# neopixels.net
KiCad netlist of a schematic drawn in Altium Designer
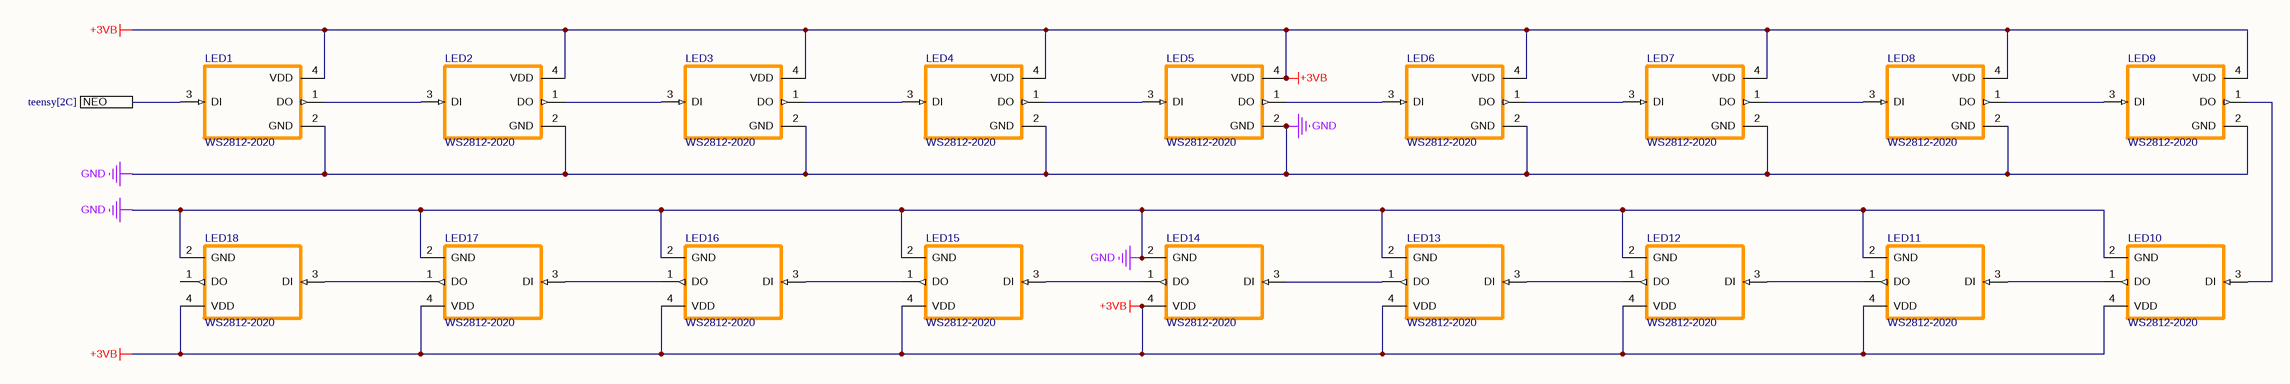
[diagram p0: neopixels.SchDoc]

(export (version "E")
  (design (tool "Eeschema 10.0.6"))
  (components
    (comp (ref "LED1")
      (value "WS2812-2020")
      (footprint "WS2812-2020")
      (libsource (lib "") (part "WS2812-2020_1"))
    )
    (comp (ref "LED2")
      (value "WS2812-2020")
      (footprint "WS2812-2020")
      (libsource (lib "") (part "WS2812-2020_1"))
    )
    (comp (ref "LED3")
      (value "WS2812-2020")
      (footprint "WS2812-2020")
      (libsource (lib "") (part "WS2812-2020_1"))
    )
    (comp (ref "LED4")
      (value "WS2812-2020")
      (footprint "WS2812-2020")
      (libsource (lib "") (part "WS2812-2020_1"))
    )
    (comp (ref "LED5")
      (value "WS2812-2020")
      (footprint "WS2812-2020")
      (libsource (lib "") (part "WS2812-2020_1"))
    )
    (comp (ref "LED6")
      (value "WS2812-2020")
      (footprint "WS2812-2020")
      (libsource (lib "") (part "WS2812-2020_1"))
    )
    (comp (ref "LED7")
      (value "WS2812-2020")
      (footprint "WS2812-2020")
      (libsource (lib "") (part "WS2812-2020_1"))
    )
    (comp (ref "LED8")
      (value "WS2812-2020")
      (footprint "WS2812-2020")
      (libsource (lib "") (part "WS2812-2020_1"))
    )
    (comp (ref "LED9")
      (value "WS2812-2020")
      (footprint "WS2812-2020")
      (libsource (lib "") (part "WS2812-2020_1"))
    )
    (comp (ref "LED10")
      (value "WS2812-2020")
      (footprint "WS2812-2020")
      (libsource (lib "RC") (part "WS2812-2020"))
    )
    (comp (ref "LED11")
      (value "WS2812-2020")
      (footprint "WS2812-2020")
      (libsource (lib "RC") (part "WS2812-2020"))
    )
    (comp (ref "LED12")
      (value "WS2812-2020")
      (footprint "WS2812-2020")
      (libsource (lib "RC") (part "WS2812-2020"))
    )
    (comp (ref "LED13")
      (value "WS2812-2020")
      (footprint "WS2812-2020")
      (libsource (lib "RC") (part "WS2812-2020"))
    )
    (comp (ref "LED14")
      (value "WS2812-2020")
      (footprint "WS2812-2020")
      (libsource (lib "RC") (part "WS2812-2020"))
    )
    (comp (ref "LED15")
      (value "WS2812-2020")
      (footprint "WS2812-2020")
      (libsource (lib "RC") (part "WS2812-2020"))
    )
    (comp (ref "LED16")
      (value "WS2812-2020")
      (footprint "WS2812-2020")
      (libsource (lib "RC") (part "WS2812-2020"))
    )
    (comp (ref "LED17")
      (value "WS2812-2020")
      (footprint "WS2812-2020")
      (libsource (lib "RC") (part "WS2812-2020"))
    )
    (comp (ref "LED18")
      (value "WS2812-2020")
      (footprint "WS2812-2020")
      (libsource (lib "RC") (part "WS2812-2020"))
    )
  )
  (nets
    (net (code "1") (name "+3VB") (class "Default")
      (node (ref "LED1") (pin "4") (pinfunction "VDD_4") (pintype "power_in"))
      (node (ref "LED10") (pin "4") (pinfunction "VDD_4") (pintype "power_in"))
      (node (ref "LED11") (pin "4") (pinfunction "VDD_4") (pintype "power_in"))
      (node (ref "LED12") (pin "4") (pinfunction "VDD_4") (pintype "power_in"))
      (node (ref "LED13") (pin "4") (pinfunction "VDD_4") (pintype "power_in"))
      (node (ref "LED14") (pin "4") (pinfunction "VDD_4") (pintype "power_in"))
      (node (ref "LED15") (pin "4") (pinfunction "VDD_4") (pintype "power_in"))
      (node (ref "LED16") (pin "4") (pinfunction "VDD_4") (pintype "power_in"))
      (node (ref "LED17") (pin "4") (pinfunction "VDD_4") (pintype "power_in"))
      (node (ref "LED18") (pin "4") (pinfunction "VDD_4") (pintype "power_in"))
      (node (ref "LED2") (pin "4") (pinfunction "VDD_4") (pintype "power_in"))
      (node (ref "LED3") (pin "4") (pinfunction "VDD_4") (pintype "power_in"))
      (node (ref "LED4") (pin "4") (pinfunction "VDD_4") (pintype "power_in"))
      (node (ref "LED5") (pin "4") (pinfunction "VDD_4") (pintype "power_in"))
      (node (ref "LED6") (pin "4") (pinfunction "VDD_4") (pintype "power_in"))
      (node (ref "LED7") (pin "4") (pinfunction "VDD_4") (pintype "power_in"))
      (node (ref "LED8") (pin "4") (pinfunction "VDD_4") (pintype "power_in"))
      (node (ref "LED9") (pin "4") (pinfunction "VDD_4") (pintype "power_in"))
    )
    (net (code "2") (name "/NEO") (class "Default")
      (node (ref "LED1") (pin "3") (pinfunction "DI_3") (pintype "input"))
    )
    (net (code "3") (name "GND") (class "Default")
      (node (ref "LED1") (pin "2") (pinfunction "GND_2") (pintype "power_in"))
      (node (ref "LED10") (pin "2") (pinfunction "GND_2") (pintype "power_in"))
      (node (ref "LED11") (pin "2") (pinfunction "GND_2") (pintype "power_in"))
      (node (ref "LED12") (pin "2") (pinfunction "GND_2") (pintype "power_in"))
      (node (ref "LED13") (pin "2") (pinfunction "GND_2") (pintype "power_in"))
      (node (ref "LED14") (pin "2") (pinfunction "GND_2") (pintype "power_in"))
      (node (ref "LED15") (pin "2") (pinfunction "GND_2") (pintype "power_in"))
      (node (ref "LED16") (pin "2") (pinfunction "GND_2") (pintype "power_in"))
      (node (ref "LED17") (pin "2") (pinfunction "GND_2") (pintype "power_in"))
      (node (ref "LED18") (pin "2") (pinfunction "GND_2") (pintype "power_in"))
      (node (ref "LED2") (pin "2") (pinfunction "GND_2") (pintype "power_in"))
      (node (ref "LED3") (pin "2") (pinfunction "GND_2") (pintype "power_in"))
      (node (ref "LED4") (pin "2") (pinfunction "GND_2") (pintype "power_in"))
      (node (ref "LED5") (pin "2") (pinfunction "GND_2") (pintype "power_in"))
      (node (ref "LED6") (pin "2") (pinfunction "GND_2") (pintype "power_in"))
      (node (ref "LED7") (pin "2") (pinfunction "GND_2") (pintype "power_in"))
      (node (ref "LED8") (pin "2") (pinfunction "GND_2") (pintype "power_in"))
      (node (ref "LED9") (pin "2") (pinfunction "GND_2") (pintype "power_in"))
    )
    (net (code "4") (name "Net-(LED1-DO)") (class "Default")
      (node (ref "LED1") (pin "1") (pinfunction "DO_1") (pintype "output"))
      (node (ref "LED2") (pin "3") (pinfunction "DI_3") (pintype "input"))
    )
    (net (code "5") (name "Net-(LED2-DO)") (class "Default")
      (node (ref "LED2") (pin "1") (pinfunction "DO_1") (pintype "output"))
      (node (ref "LED3") (pin "3") (pinfunction "DI_3") (pintype "input"))
    )
    (net (code "6") (name "Net-(LED3-DO)") (class "Default")
      (node (ref "LED3") (pin "1") (pinfunction "DO_1") (pintype "output"))
      (node (ref "LED4") (pin "3") (pinfunction "DI_3") (pintype "input"))
    )
    (net (code "7") (name "Net-(LED4-DO)") (class "Default")
      (node (ref "LED4") (pin "1") (pinfunction "DO_1") (pintype "output"))
      (node (ref "LED5") (pin "3") (pinfunction "DI_3") (pintype "input"))
    )
    (net (code "8") (name "Net-(LED5-DO)") (class "Default")
      (node (ref "LED5") (pin "1") (pinfunction "DO_1") (pintype "output"))
      (node (ref "LED6") (pin "3") (pinfunction "DI_3") (pintype "input"))
    )
    (net (code "9") (name "Net-(LED6-DO)") (class "Default")
      (node (ref "LED6") (pin "1") (pinfunction "DO_1") (pintype "output"))
      (node (ref "LED7") (pin "3") (pinfunction "DI_3") (pintype "input"))
    )
    (net (code "10") (name "Net-(LED7-DO)") (class "Default")
      (node (ref "LED7") (pin "1") (pinfunction "DO_1") (pintype "output"))
      (node (ref "LED8") (pin "3") (pinfunction "DI_3") (pintype "input"))
    )
    (net (code "11") (name "Net-(LED8-DO)") (class "Default")
      (node (ref "LED8") (pin "1") (pinfunction "DO_1") (pintype "output"))
      (node (ref "LED9") (pin "3") (pinfunction "DI_3") (pintype "input"))
    )
    (net (code "12") (name "Net-(LED10-DI)") (class "Default")
      (node (ref "LED10") (pin "3") (pinfunction "DI_3") (pintype "input"))
      (node (ref "LED9") (pin "1") (pinfunction "DO_1") (pintype "output"))
    )
    (net (code "13") (name "Net-(LED10-DO)") (class "Default")
      (node (ref "LED10") (pin "1") (pinfunction "DO_1") (pintype "output"))
      (node (ref "LED11") (pin "3") (pinfunction "DI_3") (pintype "input"))
    )
    (net (code "14") (name "Net-(LED11-DO)") (class "Default")
      (node (ref "LED11") (pin "1") (pinfunction "DO_1") (pintype "output"))
      (node (ref "LED12") (pin "3") (pinfunction "DI_3") (pintype "input"))
    )
    (net (code "15") (name "Net-(LED12-DO)") (class "Default")
      (node (ref "LED12") (pin "1") (pinfunction "DO_1") (pintype "output"))
      (node (ref "LED13") (pin "3") (pinfunction "DI_3") (pintype "input"))
    )
    (net (code "16") (name "Net-(LED13-DO)") (class "Default")
      (node (ref "LED13") (pin "1") (pinfunction "DO_1") (pintype "output"))
      (node (ref "LED14") (pin "3") (pinfunction "DI_3") (pintype "input"))
    )
    (net (code "17") (name "Net-(LED14-DO)") (class "Default")
      (node (ref "LED14") (pin "1") (pinfunction "DO_1") (pintype "output"))
      (node (ref "LED15") (pin "3") (pinfunction "DI_3") (pintype "input"))
    )
    (net (code "18") (name "Net-(LED15-DO)") (class "Default")
      (node (ref "LED15") (pin "1") (pinfunction "DO_1") (pintype "output"))
      (node (ref "LED16") (pin "3") (pinfunction "DI_3") (pintype "input"))
    )
    (net (code "19") (name "Net-(LED16-DO)") (class "Default")
      (node (ref "LED16") (pin "1") (pinfunction "DO_1") (pintype "output"))
      (node (ref "LED17") (pin "3") (pinfunction "DI_3") (pintype "input"))
    )
    (net (code "20") (name "Net-(LED17-DO)") (class "Default")
      (node (ref "LED17") (pin "1") (pinfunction "DO_1") (pintype "output"))
      (node (ref "LED18") (pin "3") (pinfunction "DI_3") (pintype "input"))
    )
    (net (code "21") (name "unconnected-(LED18-DO-Pad1)") (class "Default")
      (node (ref "LED18") (pin "1") (pinfunction "DO_1") (pintype "output"))
    )
  )
)
